# LcsNodes-Turnout-Dock-B_00_01.net
KiCad netlist of a schematic drawn in EasyEDA
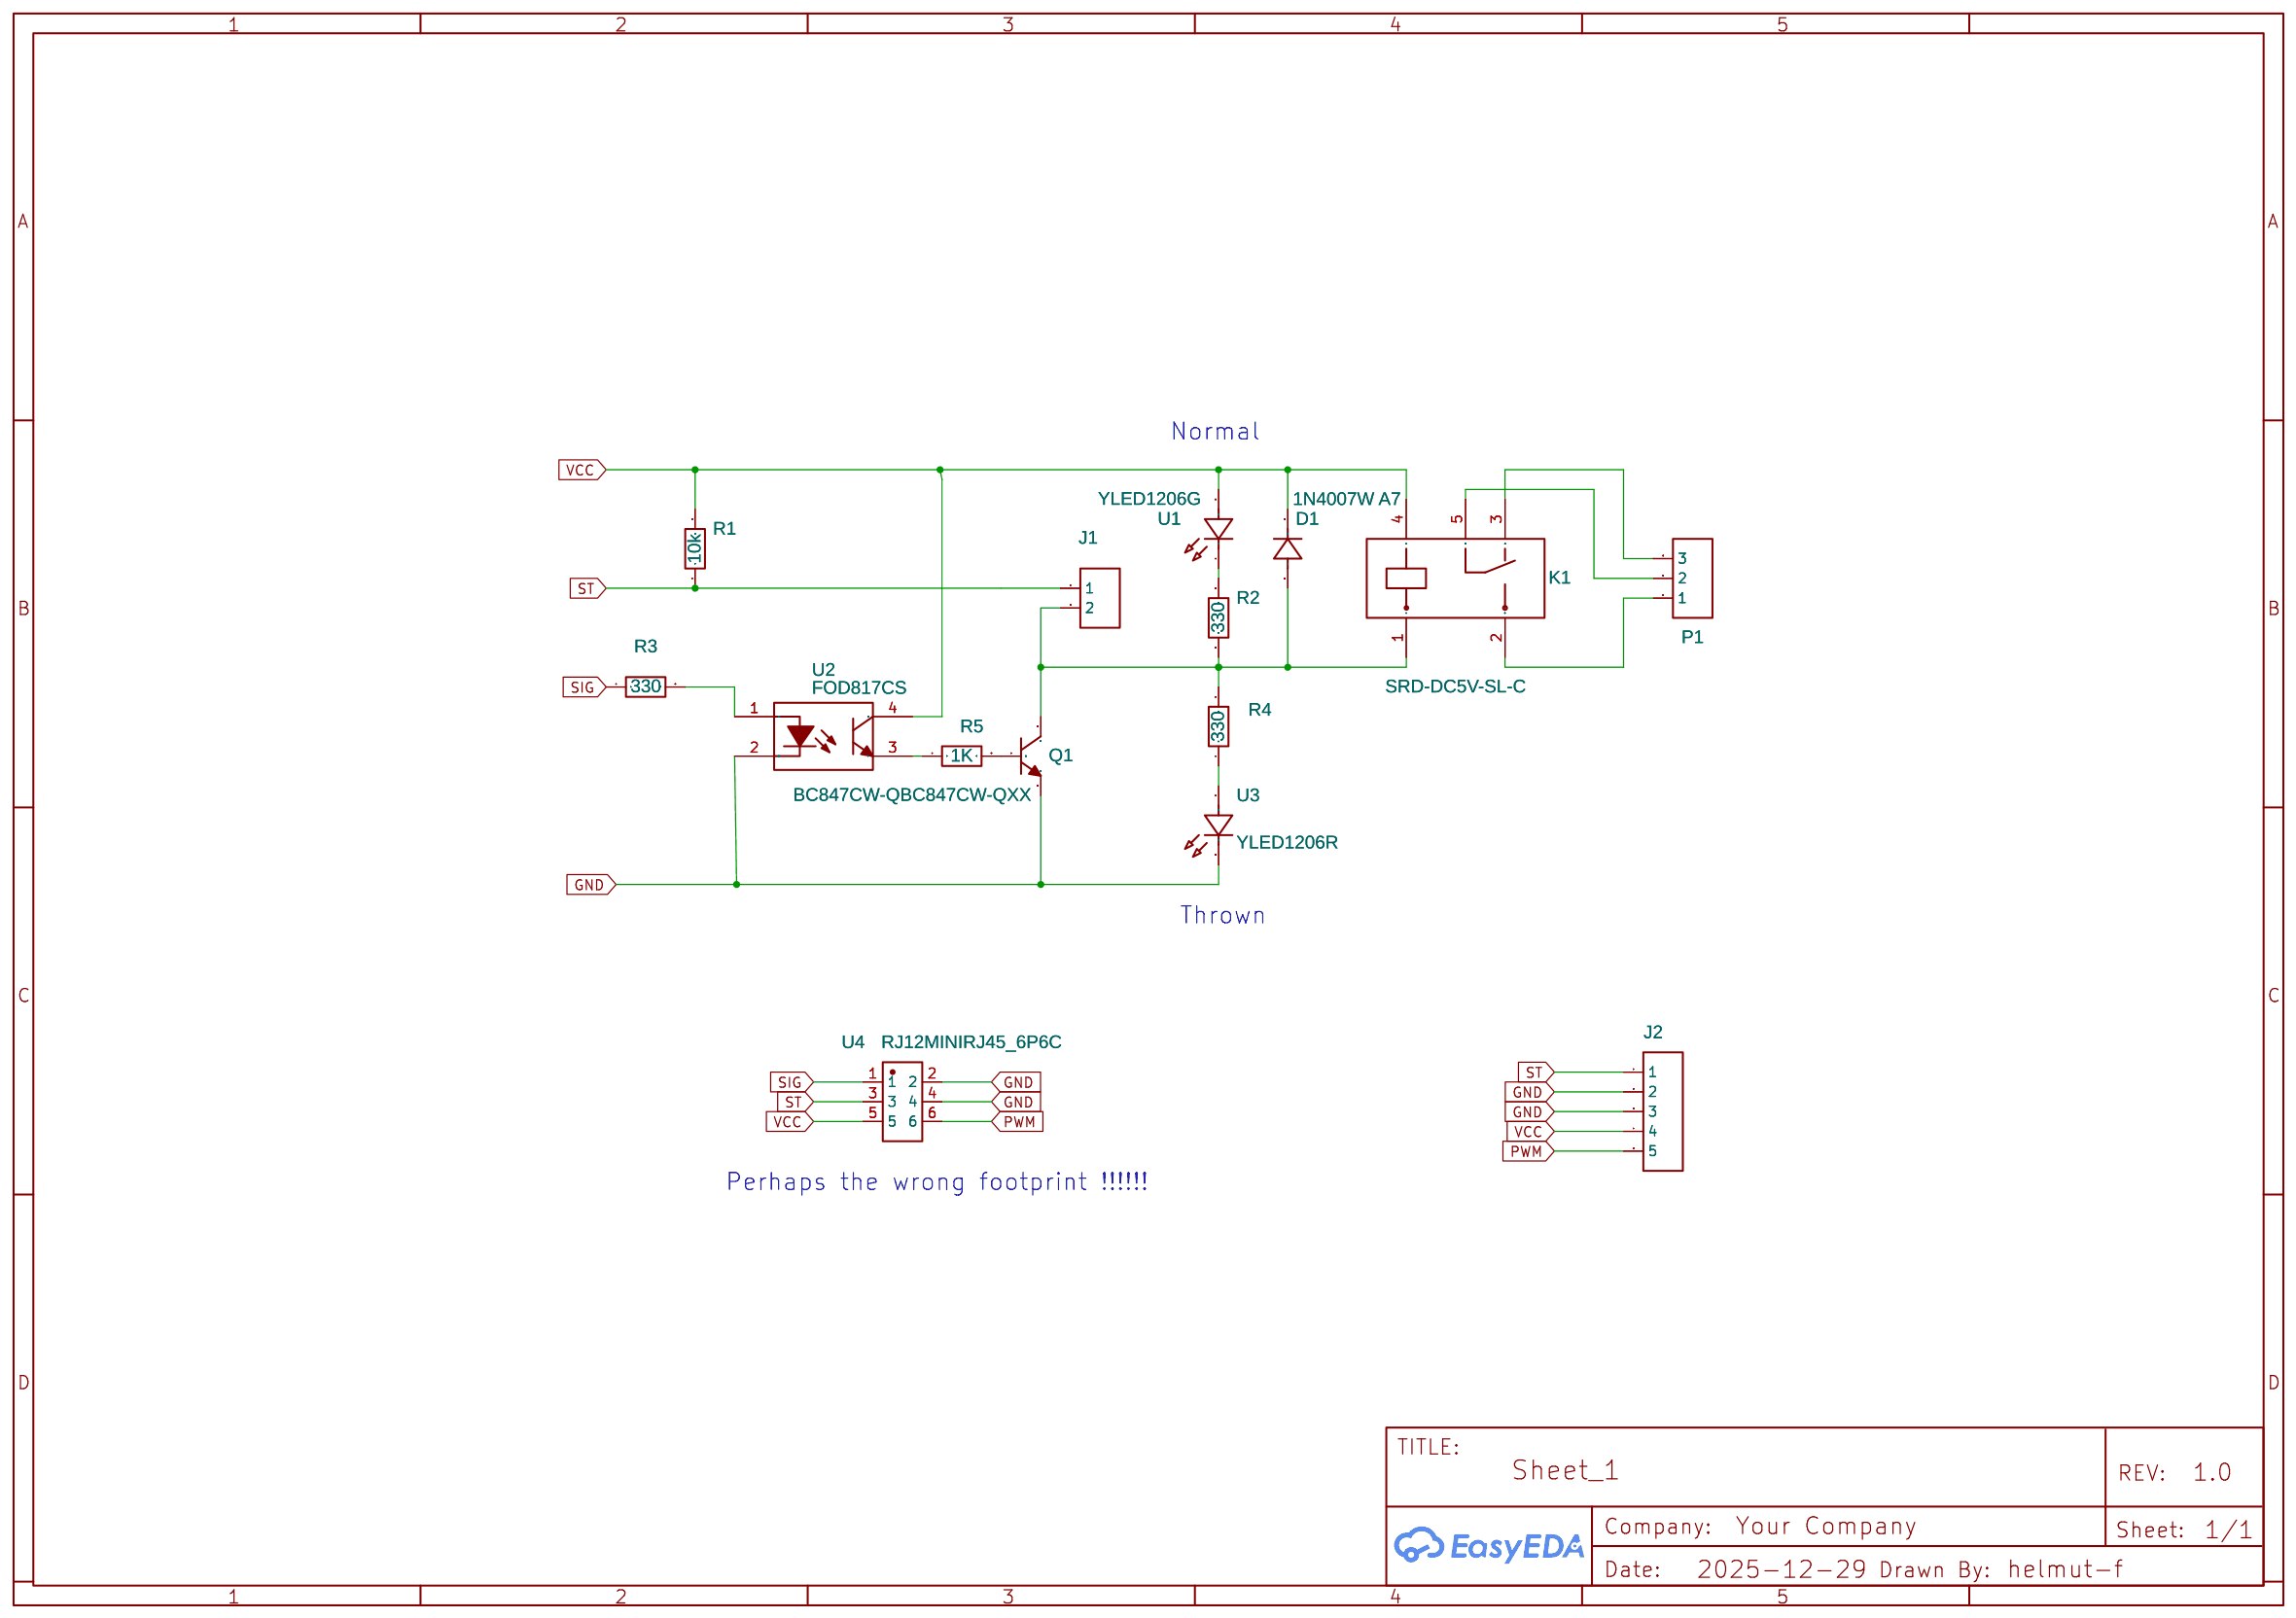
[diagram p0: schematic sheet]

(export (version "E")
  (design (tool "Eeschema 10.0.6"))
  (components
    (comp (ref "D1")
      (value "1N4007W A7")
      (fields (field (name "Manufacturer") "JSMSEMI(杰盛微)"))
      (libsource (lib "") (part "1N4007W A7"))
    )
    (comp (ref "J1") (value "HDR-M-2.54_1x2") (libsource (lib "") (part "HDR-M-2.54_1x2")))
    (comp (ref "J2") (value "HDR-M-2.54_1x5") (libsource (lib "") (part "HDR-M-2.54_1x5")))
    (comp (ref "K1") (value "SRD-DC5V-SL-C") (libsource (lib "") (part "SRD-DC5V-SL-C")))
    (comp (ref "P1") (value "CONN-TH_3P-P5.08") (libsource (lib "") (part "CONN-TH_3P-P5.08")))
    (comp (ref "Q1")
      (value "BC847CW-QBC847CW-QXX")
      (fields (field (name "Manufacturer") "Nexperia(安世)"))
      (libsource (lib "") (part "BC847CW-QBC847CW-QXX"))
    )
    (comp (ref "R1") (value "10k") (libsource (lib "") (part "R_0805_EU")))
    (comp (ref "R2") (value "330") (libsource (lib "") (part "R_0805_EU")))
    (comp (ref "R3") (value "330") (libsource (lib "") (part "R_0805_EU_1")))
    (comp (ref "R4") (value "330") (libsource (lib "") (part "R_0805_EU")))
    (comp (ref "R5") (value "1K") (libsource (lib "") (part "R_0805_EU_1")))
    (comp (ref "U1")
      (value "YLED1206G")
      (fields (field (name "Manufacturer") "YONGYUTAI(永裕泰)"))
      (libsource (lib "") (part "YLED1206G"))
    )
    (comp (ref "U2")
      (value "FOD817CS")
      (fields (field (name "Manufacturer") "onsemi(安森美)"))
      (libsource (lib "") (part "FOD817CS"))
    )
    (comp (ref "U3")
      (value "YLED1206R")
      (fields (field (name "Manufacturer") "YONGYUTAI(永裕泰)"))
      (libsource (lib "") (part "YLED1206R"))
    )
    (comp (ref "U4") (value "RJ12MINIRJ45_6P6C") (libsource (lib "") (part "RJ12MINIRJ45_6P6C")))
  )
  (nets
    (net (code "1") (name "GND") (class "Default")
      (node (ref "J2") (pin "2") (pinfunction "2_2") (pintype "unspecified"))
      (node (ref "J2") (pin "3") (pinfunction "3_3") (pintype "unspecified"))
      (node (ref "Q1") (pin "2") (pinfunction "E_2") (pintype "unspecified"))
      (node (ref "U2") (pin "2") (pinfunction "C_2") (pintype "unspecified"))
      (node (ref "U3") (pin "2") (pinfunction "2_2") (pintype "unspecified"))
      (node (ref "U4") (pin "2") (pinfunction "2_2") (pintype "unspecified"))
      (node (ref "U4") (pin "4") (pinfunction "4_4") (pintype "unspecified"))
    )
    (net (code "2") (name "Net-(D1-A)") (class "Default")
      (node (ref "D1") (pin "2") (pinfunction "A_2") (pintype "unspecified"))
      (node (ref "J1") (pin "2") (pinfunction "2_2") (pintype "unspecified"))
      (node (ref "K1") (pin "1") (pinfunction "1_1") (pintype "input"))
      (node (ref "Q1") (pin "3") (pinfunction "C_3") (pintype "unspecified"))
      (node (ref "R2") (pin "1") (pinfunction "1_1") (pintype "unspecified"))
      (node (ref "R4") (pin "2") (pinfunction "2_2") (pintype "unspecified"))
    )
    (net (code "3") (name "Net-(K1-Pad2)") (class "Default")
      (node (ref "K1") (pin "2") (pinfunction "2_2") (pintype "input"))
      (node (ref "P1") (pin "1") (pinfunction "1_1") (pintype "unspecified"))
    )
    (net (code "4") (name "Net-(K1-Pad3)") (class "Default")
      (node (ref "K1") (pin "3") (pinfunction "3_3") (pintype "input"))
      (node (ref "P1") (pin "3") (pinfunction "3_3") (pintype "unspecified"))
    )
    (net (code "5") (name "Net-(K1-Pad5)") (class "Default")
      (node (ref "K1") (pin "5") (pinfunction "5_5") (pintype "input"))
      (node (ref "P1") (pin "2") (pinfunction "2_2") (pintype "unspecified"))
    )
    (net (code "6") (name "Net-(Q1-B)") (class "Default")
      (node (ref "Q1") (pin "1") (pinfunction "B_1") (pintype "unspecified"))
      (node (ref "R5") (pin "2") (pinfunction "2_2") (pintype "unspecified"))
    )
    (net (code "7") (name "Net-(R4-Pad1)") (class "Default")
      (node (ref "R4") (pin "1") (pinfunction "1_1") (pintype "unspecified"))
      (node (ref "U3") (pin "1") (pinfunction "1_1") (pintype "unspecified"))
    )
    (net (code "8") (name "Net-(U1-K)") (class "Default")
      (node (ref "R2") (pin "2") (pinfunction "2_2") (pintype "unspecified"))
      (node (ref "U1") (pin "1") (pinfunction "K_1") (pintype "unspecified"))
    )
    (net (code "9") (name "Net-(U2-A)") (class "Default")
      (node (ref "R3") (pin "2") (pinfunction "2_2") (pintype "unspecified"))
      (node (ref "U2") (pin "1") (pinfunction "A_1") (pintype "unspecified"))
    )
    (net (code "10") (name "Net-(U2-E)") (class "Default")
      (node (ref "R5") (pin "1") (pinfunction "1_1") (pintype "unspecified"))
      (node (ref "U2") (pin "3") (pinfunction "E_3") (pintype "unspecified"))
    )
    (net (code "11") (name "PWM") (class "Default")
      (node (ref "J2") (pin "5") (pinfunction "5_5") (pintype "unspecified"))
      (node (ref "U4") (pin "6") (pinfunction "6_6") (pintype "unspecified"))
    )
    (net (code "12") (name "SIG") (class "Default")
      (node (ref "R3") (pin "1") (pinfunction "1_1") (pintype "unspecified"))
      (node (ref "U4") (pin "1") (pinfunction "1_1") (pintype "unspecified"))
    )
    (net (code "13") (name "ST") (class "Default")
      (node (ref "J1") (pin "1") (pinfunction "1_1") (pintype "unspecified"))
      (node (ref "J2") (pin "1") (pinfunction "1_1") (pintype "unspecified"))
      (node (ref "R1") (pin "1") (pinfunction "1_1") (pintype "unspecified"))
      (node (ref "U4") (pin "3") (pinfunction "3_3") (pintype "unspecified"))
    )
    (net (code "14") (name "VCC") (class "Default")
      (node (ref "D1") (pin "1") (pinfunction "C_1") (pintype "unspecified"))
      (node (ref "J2") (pin "4") (pinfunction "4_4") (pintype "unspecified"))
      (node (ref "K1") (pin "4") (pinfunction "4_4") (pintype "input"))
      (node (ref "R1") (pin "2") (pinfunction "2_2") (pintype "unspecified"))
      (node (ref "U1") (pin "2") (pinfunction "A_2") (pintype "unspecified"))
      (node (ref "U2") (pin "4") (pinfunction "C_4") (pintype "unspecified"))
      (node (ref "U4") (pin "5") (pinfunction "5_5") (pintype "unspecified"))
    )
  )
)
